# Project_bird_V2_1.net
KiCad netlist of a schematic drawn in EAGLE
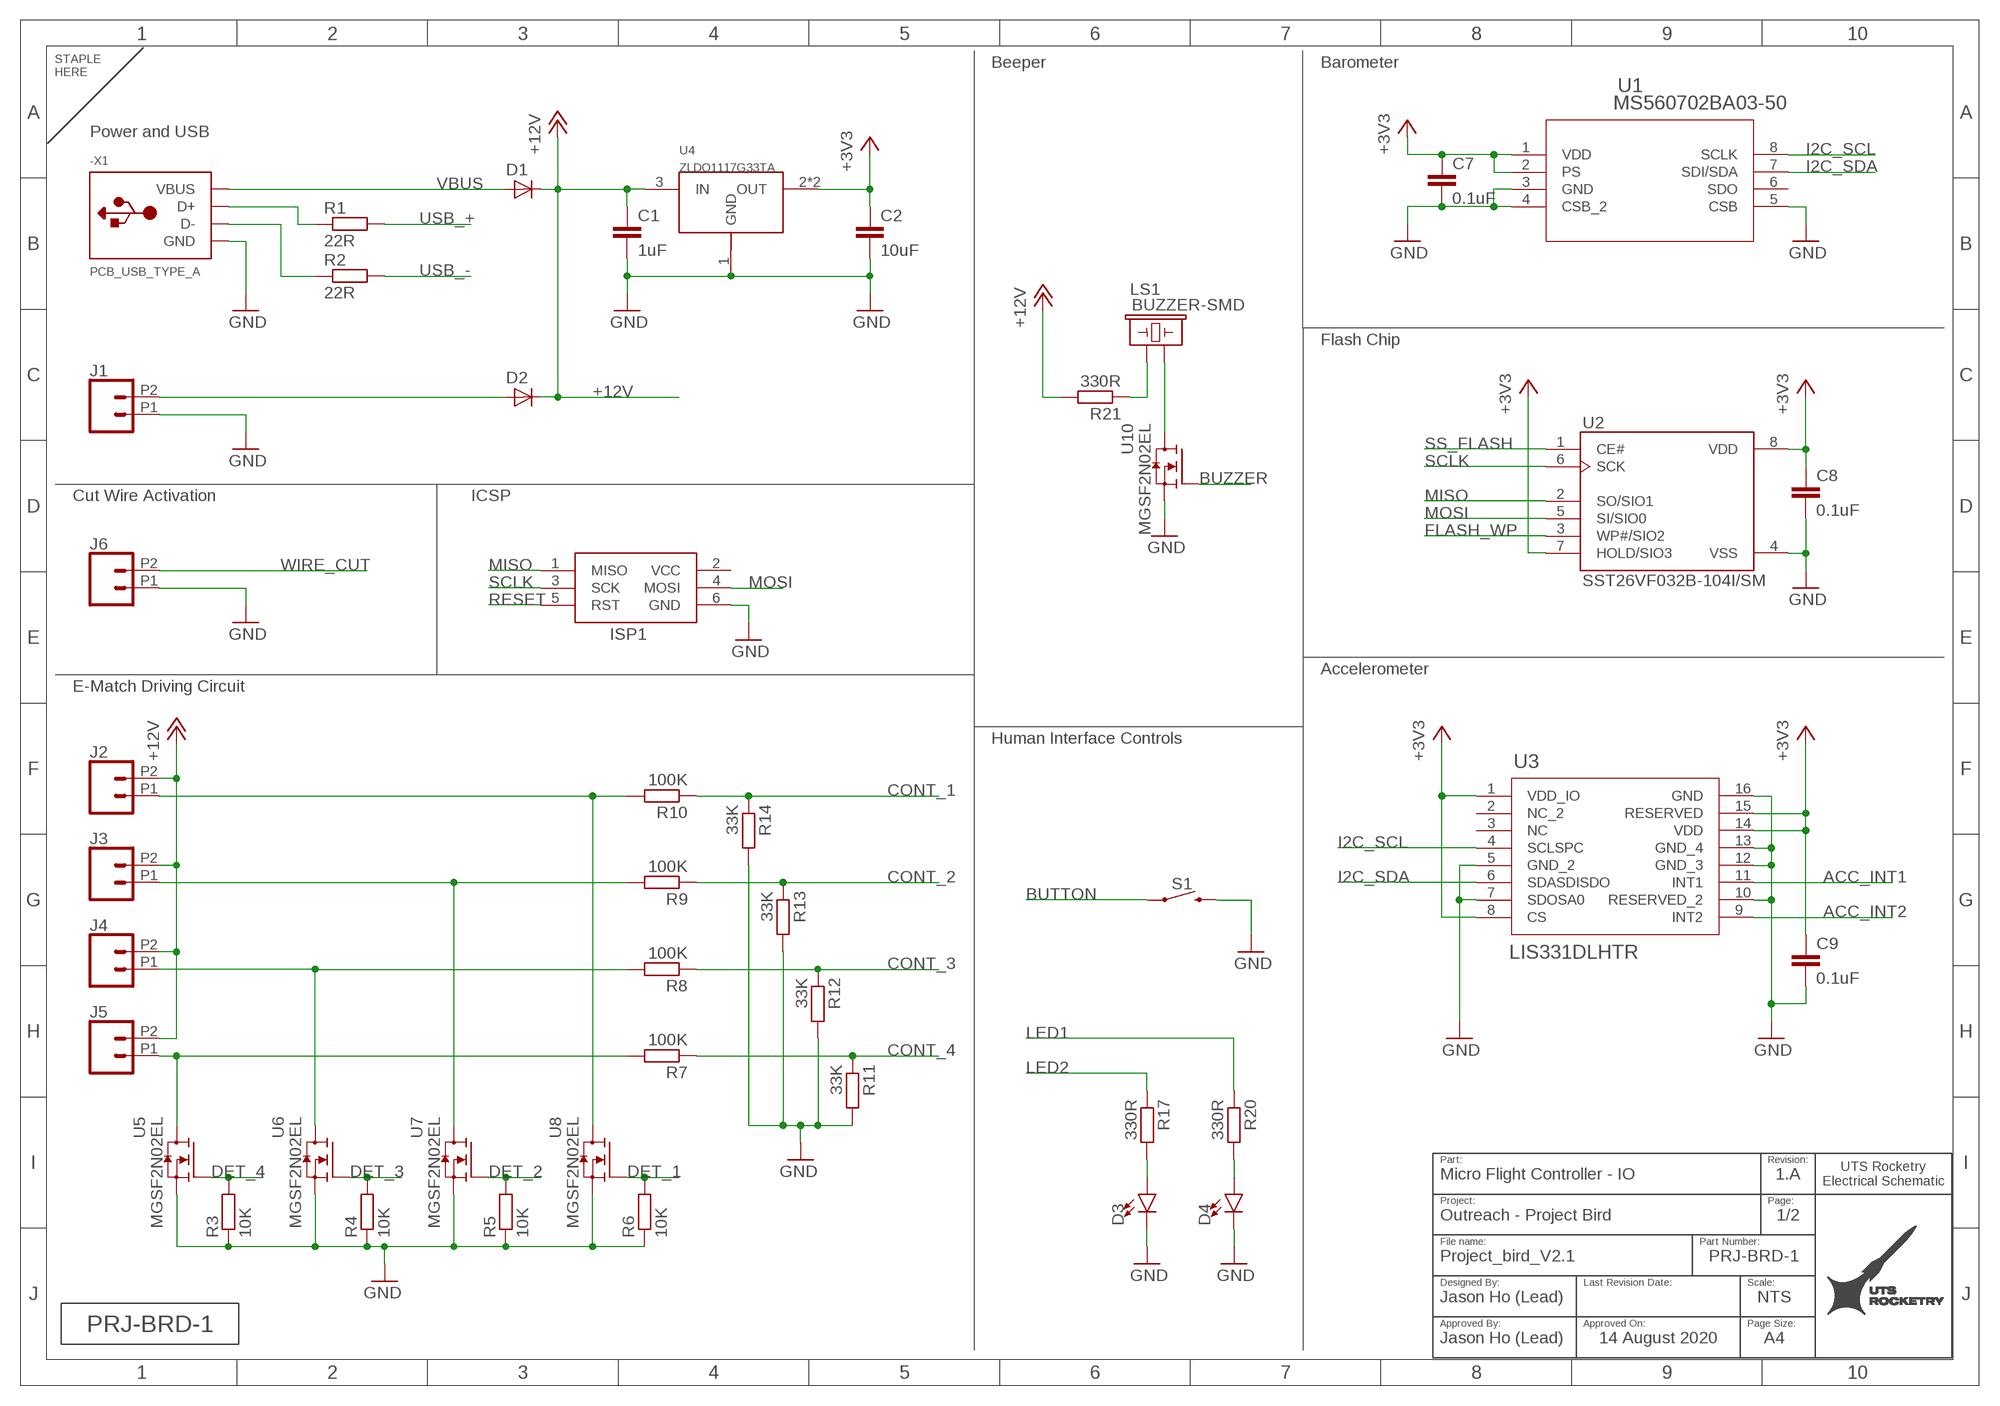
[diagram p0: schematic, sheet 1]
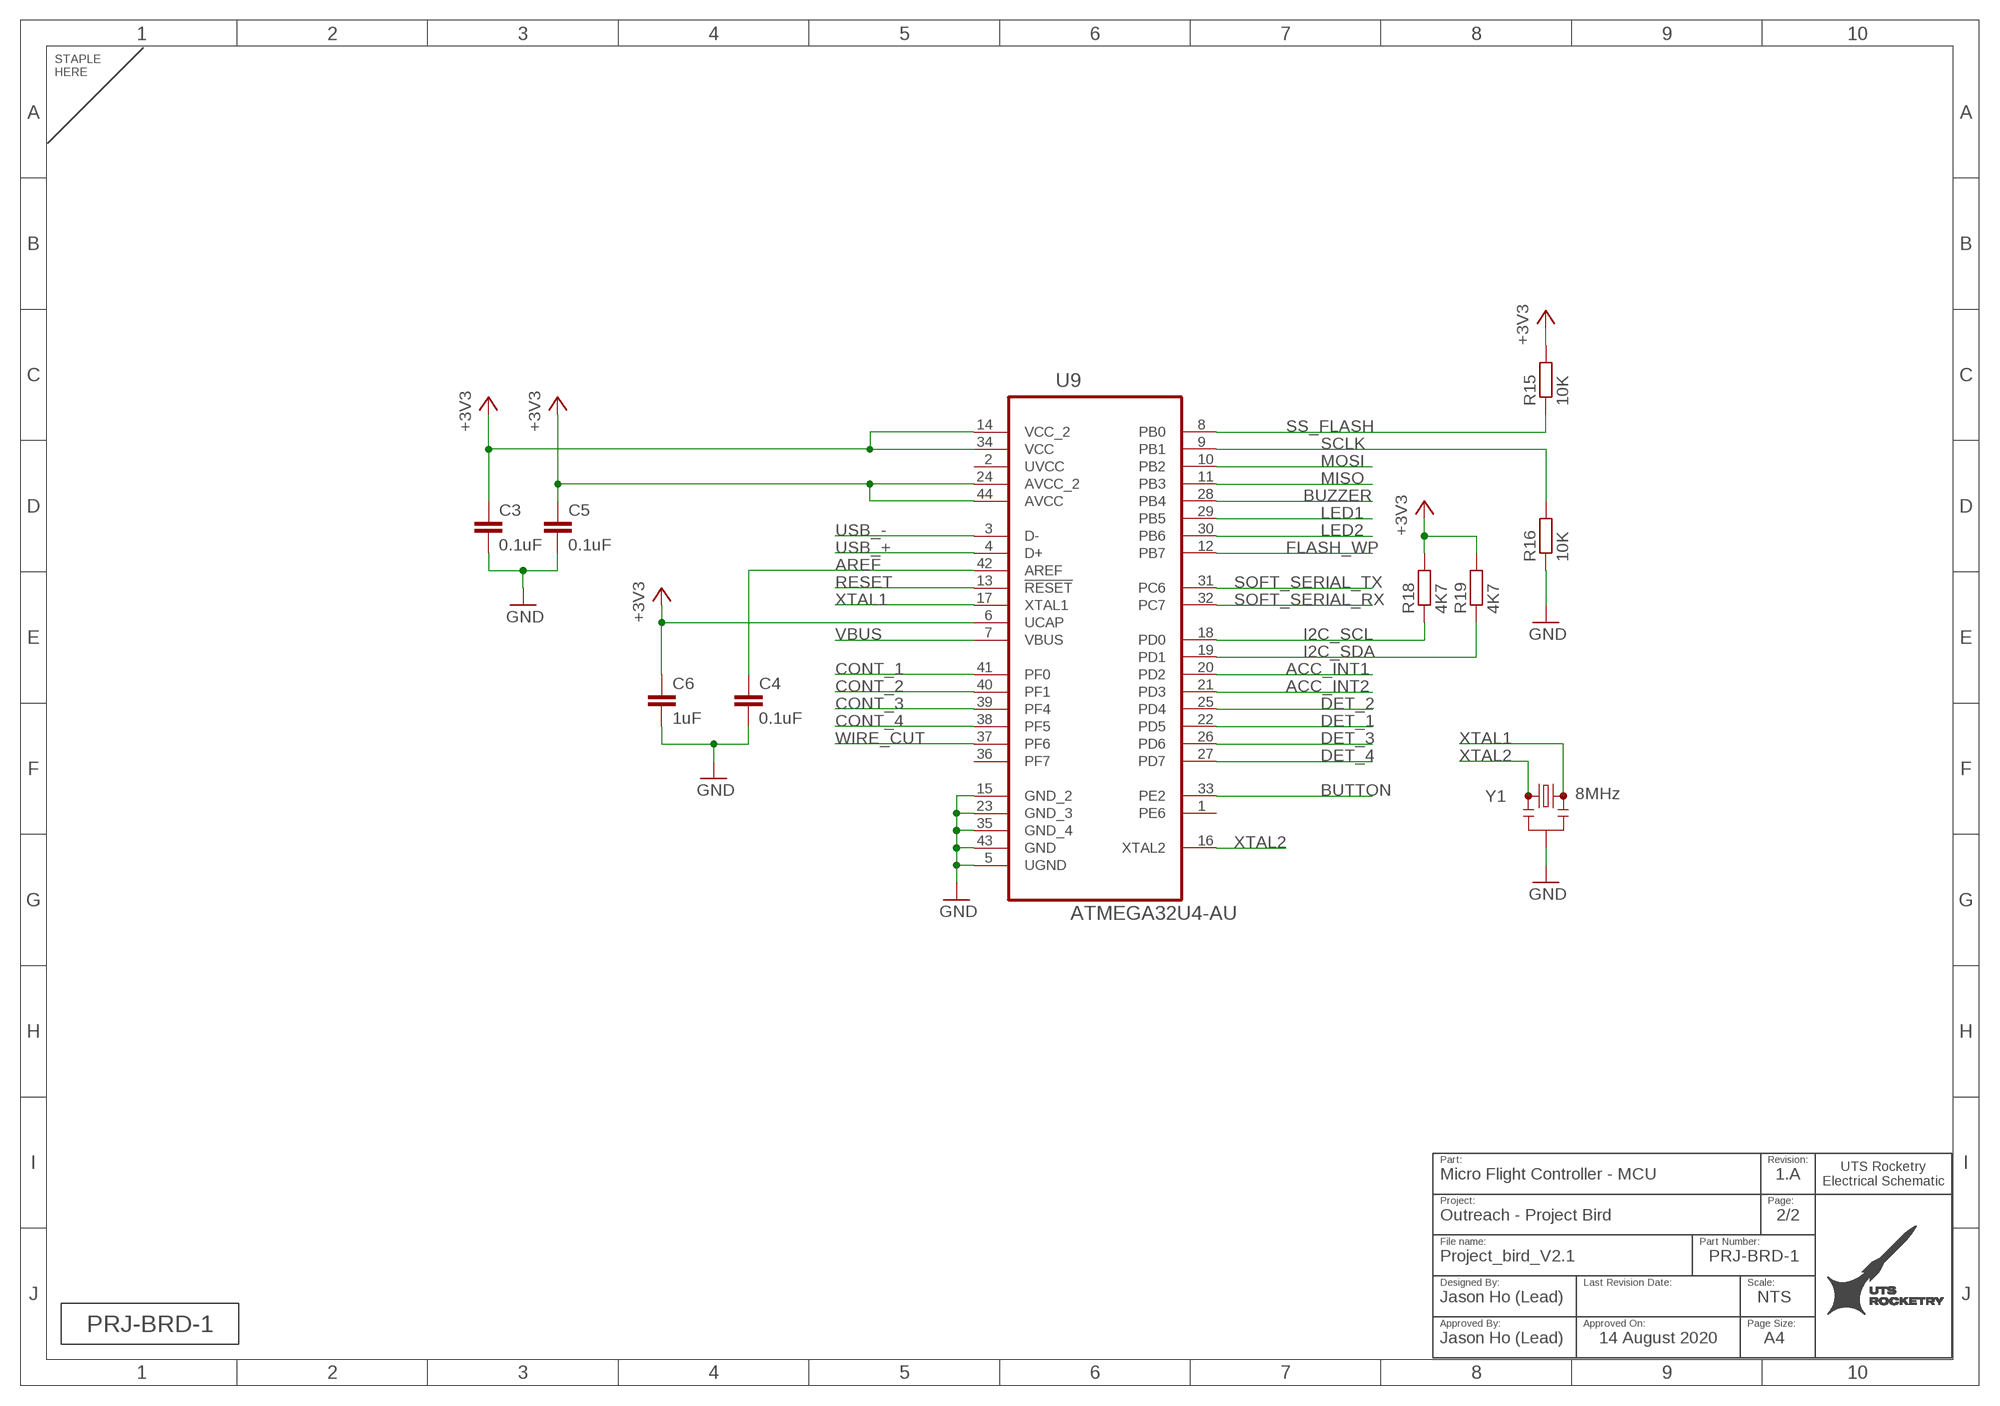
[diagram p1: schematic, sheet 2]

(export (version "E")
  (design (tool "Eeschema 10.0.6"))
  (components
    (comp (ref "C3")
      (value "0.1uF")
      (footprint "eagle-import:C0805K")
      (libsource (lib "eagle-import") (part "CAP_0805"))
    )
    (comp (ref "C4")
      (value "0.1uF")
      (footprint "eagle-import:C0805K")
      (libsource (lib "eagle-import") (part "CAP_0805"))
    )
    (comp (ref "C5")
      (value "0.1uF")
      (footprint "eagle-import:C0805K")
      (libsource (lib "eagle-import") (part "CAP_0805"))
    )
    (comp (ref "C6")
      (value "1uF")
      (footprint "eagle-import:C0805K")
      (libsource (lib "eagle-import") (part "CAP_0805"))
    )
    (comp (ref "R15")
      (value "10K")
      (footprint "eagle-import:R0805")
      (libsource (lib "eagle-import") (part "RES_0805"))
    )
    (comp (ref "R16")
      (value "10K")
      (footprint "eagle-import:R0805")
      (libsource (lib "eagle-import") (part "RES_0805"))
    )
    (comp (ref "R18")
      (value "4K7")
      (footprint "eagle-import:R0805")
      (libsource (lib "eagle-import") (part "RES_0805"))
    )
    (comp (ref "R19")
      (value "4K7")
      (footprint "eagle-import:R0805")
      (libsource (lib "eagle-import") (part "RES_0805"))
    )
    (comp (ref "U9")
      (value "ATMEGA32U4-AU")
      (footprint "eagle-import:QFP80P1200X1200X120-44N")
      (fields (field (name "MF") "Microchip Technology / Atmel"))
      (libsource (lib "eagle-import") (part "ATMEGA32U4-AU"))
    )
    (comp (ref "Y1")
      (value "8MHz")
      (footprint "eagle-import:RESONATOR-SMD-3.2X1.3")
      (libsource (lib "eagle-import") (part "RESONATOR-CSTCE8M00G55-R0"))
    )
    (comp (ref "-X1")
      (value "PCB_USB_TYPE_A")
      (footprint "eagle-import:USB_TYPE-A")
      (libsource (lib "eagle-import") (part "PCB_USB_TYPE_A"))
    )
    (comp (ref "C1")
      (value "1uF")
      (footprint "eagle-import:C0805K")
      (libsource (lib "eagle-import") (part "CAP_0805"))
    )
    (comp (ref "C2")
      (value "10uF")
      (footprint "eagle-import:C0805K")
      (libsource (lib "eagle-import") (part "CAP_0805"))
    )
    (comp (ref "C7")
      (value "0.1uF")
      (footprint "eagle-import:C0805K")
      (libsource (lib "eagle-import") (part "CAP_0805"))
    )
    (comp (ref "C8")
      (value "0.1uF")
      (footprint "eagle-import:C0805K")
      (libsource (lib "eagle-import") (part "CAP_0805"))
    )
    (comp (ref "C9")
      (value "0.1uF")
      (footprint "eagle-import:C0805K")
      (libsource (lib "eagle-import") (part "CAP_0805"))
    )
    (comp (ref "D1")
      (value "1A")
      (footprint "eagle-import:SOD-323F")
      (libsource (lib "eagle-import") (part "DIODESOD-323F"))
    )
    (comp (ref "D2")
      (value "1A")
      (footprint "eagle-import:SOD-323F")
      (libsource (lib "eagle-import") (part "DIODESOD-323F"))
    )
    (comp (ref "D3")
      (value "LED3MM-RED")
      (footprint "eagle-import:LED_3MM")
      (libsource (lib "eagle-import") (part "LED3MM-RED"))
    )
    (comp (ref "D4")
      (value "LED3MM-YELLOW")
      (footprint "eagle-import:LED_3MM")
      (libsource (lib "eagle-import") (part "LED3MM-YELLOW"))
    )
    (comp (ref "ISP1")
      (value "AVRISP-6")
      (footprint "eagle-import:AVRISP")
      (libsource (lib "eagle-import") (part "AVRISP-6"))
    )
    (comp (ref "J1")
      (value "CONN_022.54MM_SCREWTERM")
      (footprint "eagle-import:1X02_2.54_SCREWTERM")
      (libsource (lib "eagle-import") (part "CONN_022.54MM_SCREWTERM"))
    )
    (comp (ref "J2")
      (value "CONN_022.54MM_SCREWTERM")
      (footprint "eagle-import:1X02_2.54_SCREWTERM")
      (libsource (lib "eagle-import") (part "CONN_022.54MM_SCREWTERM"))
    )
    (comp (ref "J3")
      (value "CONN_022.54MM_SCREWTERM")
      (footprint "eagle-import:1X02_2.54_SCREWTERM")
      (libsource (lib "eagle-import") (part "CONN_022.54MM_SCREWTERM"))
    )
    (comp (ref "J4")
      (value "CONN_022.54MM_SCREWTERM")
      (footprint "eagle-import:1X02_2.54_SCREWTERM")
      (libsource (lib "eagle-import") (part "CONN_022.54MM_SCREWTERM"))
    )
    (comp (ref "J5")
      (value "CONN_022.54MM_SCREWTERM")
      (footprint "eagle-import:1X02_2.54_SCREWTERM")
      (libsource (lib "eagle-import") (part "CONN_022.54MM_SCREWTERM"))
    )
    (comp (ref "J6")
      (value "CONN_022.54MM_SCREWTERM")
      (footprint "eagle-import:1X02_2.54_SCREWTERM")
      (libsource (lib "eagle-import") (part "CONN_022.54MM_SCREWTERM"))
    )
    (comp (ref "LS1")
      (value "BUZZER-SMD")
      (footprint "eagle-import:BUZZER-CCV")
      (libsource (lib "eagle-import") (part "BUZZER-SMD"))
    )
    (comp (ref "R1")
      (value "22R")
      (footprint "eagle-import:R0805")
      (libsource (lib "eagle-import") (part "RES_0805"))
    )
    (comp (ref "R2")
      (value "22R")
      (footprint "eagle-import:R0805")
      (libsource (lib "eagle-import") (part "RES_0805"))
    )
    (comp (ref "R3")
      (value "10K")
      (footprint "eagle-import:R0805")
      (libsource (lib "eagle-import") (part "RES_0805"))
    )
    (comp (ref "R4")
      (value "10K")
      (footprint "eagle-import:R0805")
      (libsource (lib "eagle-import") (part "RES_0805"))
    )
    (comp (ref "R5")
      (value "10K")
      (footprint "eagle-import:R0805")
      (libsource (lib "eagle-import") (part "RES_0805"))
    )
    (comp (ref "R6")
      (value "10K")
      (footprint "eagle-import:R0805")
      (libsource (lib "eagle-import") (part "RES_0805"))
    )
    (comp (ref "R7")
      (value "100K")
      (footprint "eagle-import:R0805")
      (libsource (lib "eagle-import") (part "RES_0805"))
    )
    (comp (ref "R8")
      (value "100K")
      (footprint "eagle-import:R0805")
      (libsource (lib "eagle-import") (part "RES_0805"))
    )
    (comp (ref "R9")
      (value "100K")
      (footprint "eagle-import:R0805")
      (libsource (lib "eagle-import") (part "RES_0805"))
    )
    (comp (ref "R10")
      (value "100K")
      (footprint "eagle-import:R0805")
      (libsource (lib "eagle-import") (part "RES_0805"))
    )
    (comp (ref "R11")
      (value "33K")
      (footprint "eagle-import:R0805")
      (libsource (lib "eagle-import") (part "RES_0805"))
    )
    (comp (ref "R12")
      (value "33K")
      (footprint "eagle-import:R0805")
      (libsource (lib "eagle-import") (part "RES_0805"))
    )
    (comp (ref "R13")
      (value "33K")
      (footprint "eagle-import:R0805")
      (libsource (lib "eagle-import") (part "RES_0805"))
    )
    (comp (ref "R14")
      (value "33K")
      (footprint "eagle-import:R0805")
      (libsource (lib "eagle-import") (part "RES_0805"))
    )
    (comp (ref "R17")
      (value "330R")
      (footprint "eagle-import:R0805")
      (libsource (lib "eagle-import") (part "RES_0805"))
    )
    (comp (ref "R20")
      (value "330R")
      (footprint "eagle-import:R0805")
      (libsource (lib "eagle-import") (part "RES_0805"))
    )
    (comp (ref "R21")
      (value "330R")
      (footprint "eagle-import:R0805")
      (libsource (lib "eagle-import") (part "RES_0805"))
    )
    (comp (ref "S1")
      (value "MOMENTARY-SWITCH-SPST")
      (footprint "eagle-import:TACTILE_SWITCH_PTH_6.0MM")
      (libsource (lib "eagle-import") (part "MOMENTARY-SWITCH-SPST"))
    )
    (comp (ref "U1")
      (value "MS560702BA03-50")
      (footprint "eagle-import:SON8_MS5611")
      (fields (field (name "COPYRIGHT") "Copyright (C) 2016 Accelerated Designs. All rights reserved"))
      (libsource (lib "eagle-import") (part "MS560702BA03-50"))
    )
    (comp (ref "U2")
      (value "SST26VF032B-104I/SM")
      (footprint "eagle-import:SOIC127P794X203-8N")
      (fields (field (name "MF") "Microchip"))
      (libsource (lib "eagle-import") (part "SST26VF032B-104I/SM"))
    )
    (comp (ref "U3")
      (value "LIS331DLHTR")
      (footprint "eagle-import:LGA-16_3X3X1MM")
      (libsource (lib "eagle-import") (part "LIS331DLHTR"))
    )
    (comp (ref "U4")
      (value "ZLDO1117G33TA")
      (footprint "eagle-import:SOT223")
      (libsource (lib "eagle-import") (part "ZLDO1117G33TA"))
    )
    (comp (ref "U5")
      (value "MGSF2N02EL")
      (footprint "eagle-import:SOT-23-3")
      (libsource (lib "eagle-import") (part "MGSF2N02EL"))
    )
    (comp (ref "U6")
      (value "MGSF2N02EL")
      (footprint "eagle-import:SOT-23-3")
      (libsource (lib "eagle-import") (part "MGSF2N02EL"))
    )
    (comp (ref "U7")
      (value "MGSF2N02EL")
      (footprint "eagle-import:SOT-23-3")
      (libsource (lib "eagle-import") (part "MGSF2N02EL"))
    )
    (comp (ref "U8")
      (value "MGSF2N02EL")
      (footprint "eagle-import:SOT-23-3")
      (libsource (lib "eagle-import") (part "MGSF2N02EL"))
    )
    (comp (ref "U10")
      (value "MGSF2N02EL")
      (footprint "eagle-import:SOT-23-3")
      (libsource (lib "eagle-import") (part "MGSF2N02EL"))
    )
  )
  (nets
    (net (code "1") (name "+3V3") (class "Default")
      (node (ref "C2") (pin "1") (pinfunction "1_1") (pintype "passive"))
      (node (ref "C3") (pin "1") (pinfunction "1_1") (pintype "passive"))
      (node (ref "C5") (pin "1") (pinfunction "1_1") (pintype "passive"))
      (node (ref "C6") (pin "1") (pinfunction "1_1") (pintype "passive"))
      (node (ref "C7") (pin "1") (pinfunction "1_1") (pintype "passive"))
      (node (ref "C8") (pin "1") (pinfunction "1_1") (pintype "passive"))
      (node (ref "C9") (pin "1") (pinfunction "1_1") (pintype "passive"))
      (node (ref "R15") (pin "2") (pinfunction "2_2") (pintype "passive"))
      (node (ref "R18") (pin "2") (pinfunction "2_2") (pintype "passive"))
      (node (ref "R19") (pin "2") (pinfunction "2_2") (pintype "passive"))
      (node (ref "U1") (pin "1") (pinfunction "VDD_1") (pintype "power_in"))
      (node (ref "U1") (pin "2") (pinfunction "PS_2") (pintype "input"))
      (node (ref "U2") (pin "7") (pinfunction "HOLD/SIO3_7") (pintype "bidirectional"))
      (node (ref "U2") (pin "8") (pinfunction "VDD_8") (pintype "power_in"))
      (node (ref "U3") (pin "1") (pinfunction "VDD_IO_1") (pintype "power_in"))
      (node (ref "U3") (pin "14") (pinfunction "VDD_14") (pintype "power_in"))
      (node (ref "U3") (pin "15") (pinfunction "RESERVED_15") (pintype "passive"))
      (node (ref "U3") (pin "8") (pinfunction "CS_8") (pintype "passive"))
      (node (ref "U4") (pin "2") (pinfunction "OUT_2") (pintype "power_in"))
      (node (ref "U4") (pin "4") (pinfunction "OUT_4") (pintype "power_in"))
      (node (ref "U9") (pin "14") (pinfunction "VCC_2_14") (pintype "power_in"))
      (node (ref "U9") (pin "24") (pinfunction "AVCC_2_24") (pintype "power_in"))
      (node (ref "U9") (pin "34") (pinfunction "VCC_34") (pintype "power_in"))
      (node (ref "U9") (pin "44") (pinfunction "AVCC_44") (pintype "power_in"))
      (node (ref "U9") (pin "6") (pinfunction "UCAP_6") (pintype "power_in"))
    )
    (net (code "2") (name "+12V") (class "Default")
      (node (ref "C1") (pin "1") (pinfunction "1_1") (pintype "passive"))
      (node (ref "D1") (pin "C") (pinfunction "C_C") (pintype "passive"))
      (node (ref "D2") (pin "C") (pinfunction "C_C") (pintype "passive"))
      (node (ref "J2") (pin "P2") (pinfunction "2_P2") (pintype "passive"))
      (node (ref "J3") (pin "P2") (pinfunction "2_P2") (pintype "passive"))
      (node (ref "J4") (pin "P2") (pinfunction "2_P2") (pintype "passive"))
      (node (ref "J5") (pin "P2") (pinfunction "2_P2") (pintype "passive"))
      (node (ref "R21") (pin "2") (pinfunction "2_2") (pintype "passive"))
      (node (ref "U4") (pin "3") (pinfunction "IN_3") (pintype "power_in"))
    )
    (net (code "3") (name "ACC_INT1") (class "Default")
      (node (ref "U3") (pin "11") (pinfunction "INT1_11") (pintype "passive"))
      (node (ref "U9") (pin "20") (pinfunction "PD2_20") (pintype "bidirectional"))
    )
    (net (code "4") (name "ACC_INT2") (class "Default")
      (node (ref "U3") (pin "9") (pinfunction "INT2_9") (pintype "passive"))
      (node (ref "U9") (pin "21") (pinfunction "PD3_21") (pintype "bidirectional"))
    )
    (net (code "5") (name "AREF") (class "Default")
      (node (ref "C4") (pin "1") (pinfunction "1_1") (pintype "passive"))
      (node (ref "U9") (pin "42") (pinfunction "AREF_42") (pintype "input"))
    )
    (net (code "6") (name "BUTTON") (class "Default")
      (node (ref "S1") (pin "1") (pinfunction "1_1") (pintype "passive"))
      (node (ref "S1") (pin "2") (pinfunction "1_2") (pintype "passive"))
      (node (ref "U9") (pin "33") (pinfunction "PE2_33") (pintype "bidirectional"))
    )
    (net (code "7") (name "BUZZER") (class "Default")
      (node (ref "U10") (pin "1") (pinfunction "G_1") (pintype "passive"))
      (node (ref "U9") (pin "28") (pinfunction "PB4_28") (pintype "bidirectional"))
    )
    (net (code "8") (name "CONT_1") (class "Default")
      (node (ref "R10") (pin "1") (pinfunction "1_1") (pintype "passive"))
      (node (ref "R14") (pin "1") (pinfunction "1_1") (pintype "passive"))
      (node (ref "U9") (pin "41") (pinfunction "PF0_41") (pintype "bidirectional"))
    )
    (net (code "9") (name "CONT_2") (class "Default")
      (node (ref "R13") (pin "1") (pinfunction "1_1") (pintype "passive"))
      (node (ref "R9") (pin "1") (pinfunction "1_1") (pintype "passive"))
      (node (ref "U9") (pin "40") (pinfunction "PF1_40") (pintype "bidirectional"))
    )
    (net (code "10") (name "CONT_3") (class "Default")
      (node (ref "R12") (pin "1") (pinfunction "1_1") (pintype "passive"))
      (node (ref "R8") (pin "1") (pinfunction "1_1") (pintype "passive"))
      (node (ref "U9") (pin "39") (pinfunction "PF4_39") (pintype "bidirectional"))
    )
    (net (code "11") (name "CONT_4") (class "Default")
      (node (ref "R11") (pin "1") (pinfunction "1_1") (pintype "passive"))
      (node (ref "R7") (pin "1") (pinfunction "1_1") (pintype "passive"))
      (node (ref "U9") (pin "38") (pinfunction "PF5_38") (pintype "bidirectional"))
    )
    (net (code "12") (name "DET_1") (class "Default")
      (node (ref "R6") (pin "2") (pinfunction "2_2") (pintype "passive"))
      (node (ref "U8") (pin "1") (pinfunction "G_1") (pintype "passive"))
      (node (ref "U9") (pin "22") (pinfunction "PD5_22") (pintype "bidirectional"))
    )
    (net (code "13") (name "DET_2") (class "Default")
      (node (ref "R5") (pin "2") (pinfunction "2_2") (pintype "passive"))
      (node (ref "U7") (pin "1") (pinfunction "G_1") (pintype "passive"))
      (node (ref "U9") (pin "25") (pinfunction "PD4_25") (pintype "bidirectional"))
    )
    (net (code "14") (name "DET_3") (class "Default")
      (node (ref "R4") (pin "2") (pinfunction "2_2") (pintype "passive"))
      (node (ref "U6") (pin "1") (pinfunction "G_1") (pintype "passive"))
      (node (ref "U9") (pin "26") (pinfunction "PD6_26") (pintype "bidirectional"))
    )
    (net (code "15") (name "DET_4") (class "Default")
      (node (ref "R3") (pin "2") (pinfunction "2_2") (pintype "passive"))
      (node (ref "U5") (pin "1") (pinfunction "G_1") (pintype "passive"))
      (node (ref "U9") (pin "27") (pinfunction "PD7_27") (pintype "bidirectional"))
    )
    (net (code "16") (name "FLASH_WP") (class "Default")
      (node (ref "U2") (pin "3") (pinfunction "WP#/SIO2_3") (pintype "bidirectional"))
      (node (ref "U9") (pin "12") (pinfunction "PB7_12") (pintype "bidirectional"))
    )
    (net (code "17") (name "GND") (class "Default")
      (node (ref "-X1") (pin "GND") (pinfunction "GND_GND") (pintype "power_in"))
      (node (ref "C1") (pin "2") (pinfunction "2_2") (pintype "passive"))
      (node (ref "C2") (pin "2") (pinfunction "2_2") (pintype "passive"))
      (node (ref "C3") (pin "2") (pinfunction "2_2") (pintype "passive"))
      (node (ref "C4") (pin "2") (pinfunction "2_2") (pintype "passive"))
      (node (ref "C5") (pin "2") (pinfunction "2_2") (pintype "passive"))
      (node (ref "C6") (pin "2") (pinfunction "2_2") (pintype "passive"))
      (node (ref "C7") (pin "2") (pinfunction "2_2") (pintype "passive"))
      (node (ref "C8") (pin "2") (pinfunction "2_2") (pintype "passive"))
      (node (ref "C9") (pin "2") (pinfunction "2_2") (pintype "passive"))
      (node (ref "D3") (pin "K") (pinfunction "C_K") (pintype "passive"))
      (node (ref "D4") (pin "K") (pinfunction "C_K") (pintype "passive"))
      (node (ref "ISP1") (pin "6") (pinfunction "GND_6") (pintype "power_in"))
      (node (ref "J1") (pin "P1") (pinfunction "1_P1") (pintype "passive"))
      (node (ref "J6") (pin "P1") (pinfunction "1_P1") (pintype "passive"))
      (node (ref "R11") (pin "2") (pinfunction "2_2") (pintype "passive"))
      (node (ref "R12") (pin "2") (pinfunction "2_2") (pintype "passive"))
      (node (ref "R13") (pin "2") (pinfunction "2_2") (pintype "passive"))
      (node (ref "R14") (pin "2") (pinfunction "2_2") (pintype "passive"))
      (node (ref "R16") (pin "1") (pinfunction "1_1") (pintype "passive"))
      (node (ref "R3") (pin "1") (pinfunction "1_1") (pintype "passive"))
      (node (ref "R4") (pin "1") (pinfunction "1_1") (pintype "passive"))
      (node (ref "R5") (pin "1") (pinfunction "1_1") (pintype "passive"))
      (node (ref "R6") (pin "1") (pinfunction "1_1") (pintype "passive"))
      (node (ref "S1") (pin "3") (pinfunction "2_3") (pintype "passive"))
      (node (ref "S1") (pin "4") (pinfunction "2_4") (pintype "passive"))
      (node (ref "U1") (pin "3") (pinfunction "GND_3") (pintype "passive"))
      (node (ref "U1") (pin "4") (pinfunction "CSB_2_4") (pintype "input"))
      (node (ref "U1") (pin "5") (pinfunction "CSB_5") (pintype "input"))
      (node (ref "U10") (pin "2") (pinfunction "S_2") (pintype "passive"))
      (node (ref "U2") (pin "4") (pinfunction "VSS_4") (pintype "power_in"))
      (node (ref "U3") (pin "10") (pinfunction "RESERVED_2_10") (pintype "passive"))
      (node (ref "U3") (pin "12") (pinfunction "GND_3_12") (pintype "power_in"))
      (node (ref "U3") (pin "13") (pinfunction "GND_4_13") (pintype "power_in"))
      (node (ref "U3") (pin "16") (pinfunction "GND_16") (pintype "power_in"))
      (node (ref "U3") (pin "5") (pinfunction "GND_2_5") (pintype "power_in"))
      (node (ref "U3") (pin "7") (pinfunction "SDOSA0_7") (pintype "output"))
      (node (ref "U4") (pin "1") (pinfunction "GND_1") (pintype "power_in"))
      (node (ref "U5") (pin "2") (pinfunction "S_2") (pintype "passive"))
      (node (ref "U6") (pin "2") (pinfunction "S_2") (pintype "passive"))
      (node (ref "U7") (pin "2") (pinfunction "S_2") (pintype "passive"))
      (node (ref "U8") (pin "2") (pinfunction "S_2") (pintype "passive"))
      (node (ref "U9") (pin "15") (pinfunction "GND_2_15") (pintype "passive"))
      (node (ref "U9") (pin "23") (pinfunction "GND_3_23") (pintype "passive"))
      (node (ref "U9") (pin "35") (pinfunction "GND_4_35") (pintype "passive"))
      (node (ref "U9") (pin "43") (pinfunction "GND_43") (pintype "passive"))
      (node (ref "U9") (pin "5") (pinfunction "UGND_5") (pintype "passive"))
      (node (ref "Y1") (pin "2") (pinfunction "2_2") (pintype "passive"))
    )
    (net (code "18") (name "I2C_SCL") (class "Default")
      (node (ref "R18") (pin "1") (pinfunction "1_1") (pintype "passive"))
      (node (ref "U1") (pin "8") (pinfunction "SCLK_8") (pintype "bidirectional"))
      (node (ref "U3") (pin "4") (pinfunction "SCLSPC_4") (pintype "passive"))
      (node (ref "U9") (pin "18") (pinfunction "PD0_18") (pintype "bidirectional"))
    )
    (net (code "19") (name "I2C_SDA") (class "Default")
      (node (ref "R19") (pin "1") (pinfunction "1_1") (pintype "passive"))
      (node (ref "U1") (pin "7") (pinfunction "SDI/SDA_7") (pintype "bidirectional"))
      (node (ref "U3") (pin "6") (pinfunction "SDASDISDO_6") (pintype "bidirectional"))
      (node (ref "U9") (pin "19") (pinfunction "PD1_19") (pintype "bidirectional"))
    )
    (net (code "20") (name "LED1") (class "Default")
      (node (ref "R20") (pin "1") (pinfunction "1_1") (pintype "passive"))
      (node (ref "U9") (pin "29") (pinfunction "PB5_29") (pintype "bidirectional"))
    )
    (net (code "21") (name "LED2") (class "Default")
      (node (ref "R17") (pin "1") (pinfunction "1_1") (pintype "passive"))
      (node (ref "U9") (pin "30") (pinfunction "PB6_30") (pintype "bidirectional"))
    )
    (net (code "22") (name "MISO") (class "Default")
      (node (ref "ISP1") (pin "1") (pinfunction "MISO_1") (pintype "input"))
      (node (ref "U2") (pin "2") (pinfunction "SO/SIO1_2") (pintype "bidirectional"))
      (node (ref "U9") (pin "11") (pinfunction "PB3_11") (pintype "bidirectional"))
    )
    (net (code "23") (name "MOSI") (class "Default")
      (node (ref "ISP1") (pin "4") (pinfunction "MOSI_4") (pintype "output"))
      (node (ref "U2") (pin "5") (pinfunction "SI/SIO0_5") (pintype "bidirectional"))
      (node (ref "U9") (pin "10") (pinfunction "PB2_10") (pintype "bidirectional"))
    )
    (net (code "24") (name "Net-(-X1-PadD+)") (class "Default")
      (node (ref "-X1") (pin "D+") (pinfunction "D+_D+") (pintype "bidirectional"))
      (node (ref "R1") (pin "1") (pinfunction "1_1") (pintype "passive"))
    )
    (net (code "25") (name "Net-(-X1-PadD-)") (class "Default")
      (node (ref "-X1") (pin "D-") (pinfunction "D-_D-") (pintype "bidirectional"))
      (node (ref "R2") (pin "1") (pinfunction "1_1") (pintype "passive"))
    )
    (net (code "26") (name "Net-(D3-PadA)") (class "Default")
      (node (ref "D3") (pin "A") (pinfunction "A_A") (pintype "passive"))
      (node (ref "R17") (pin "2") (pinfunction "2_2") (pintype "passive"))
    )
    (net (code "27") (name "Net-(D4-PadA)") (class "Default")
      (node (ref "D4") (pin "A") (pinfunction "A_A") (pintype "passive"))
      (node (ref "R20") (pin "2") (pinfunction "2_2") (pintype "passive"))
    )
    (net (code "28") (name "Net-(J1-2)") (class "Default")
      (node (ref "D2") (pin "A") (pinfunction "A_A") (pintype "passive"))
      (node (ref "J1") (pin "P2") (pinfunction "2_P2") (pintype "passive"))
    )
    (net (code "29") (name "Net-(J2-1)") (class "Default")
      (node (ref "J2") (pin "P1") (pinfunction "1_P1") (pintype "passive"))
      (node (ref "R10") (pin "2") (pinfunction "2_2") (pintype "passive"))
      (node (ref "U8") (pin "3") (pinfunction "D_3") (pintype "passive"))
    )
    (net (code "30") (name "Net-(J3-1)") (class "Default")
      (node (ref "J3") (pin "P1") (pinfunction "1_P1") (pintype "passive"))
      (node (ref "R9") (pin "2") (pinfunction "2_2") (pintype "passive"))
      (node (ref "U7") (pin "3") (pinfunction "D_3") (pintype "passive"))
    )
    (net (code "31") (name "Net-(J4-1)") (class "Default")
      (node (ref "J4") (pin "P1") (pinfunction "1_P1") (pintype "passive"))
      (node (ref "R8") (pin "2") (pinfunction "2_2") (pintype "passive"))
      (node (ref "U6") (pin "3") (pinfunction "D_3") (pintype "passive"))
    )
    (net (code "32") (name "Net-(J5-1)") (class "Default")
      (node (ref "J5") (pin "P1") (pinfunction "1_P1") (pintype "passive"))
      (node (ref "R7") (pin "2") (pinfunction "2_2") (pintype "passive"))
      (node (ref "U5") (pin "3") (pinfunction "D_3") (pintype "passive"))
    )
    (net (code "33") (name "Net-(LS1-1)") (class "Default")
      (node (ref "LS1") (pin "+") (pinfunction "1_+") (pintype "passive"))
      (node (ref "R21") (pin "1") (pinfunction "1_1") (pintype "passive"))
    )
    (net (code "34") (name "Net-(LS1-2)") (class "Default")
      (node (ref "LS1") (pin "-") (pinfunction "2_-") (pintype "passive"))
      (node (ref "U10") (pin "3") (pinfunction "D_3") (pintype "passive"))
    )
    (net (code "35") (name "RESET") (class "Default")
      (node (ref "ISP1") (pin "5") (pinfunction "RST_5") (pintype "output"))
      (node (ref "U9") (pin "13") (pinfunction "~{RESET}_13") (pintype "input"))
    )
    (net (code "36") (name "SCLK") (class "Default")
      (node (ref "ISP1") (pin "3") (pinfunction "SCK_3") (pintype "output"))
      (node (ref "R16") (pin "2") (pinfunction "2_2") (pintype "passive"))
      (node (ref "U2") (pin "6") (pinfunction "SCK_6") (pintype "bidirectional"))
      (node (ref "U9") (pin "9") (pinfunction "PB1_9") (pintype "bidirectional"))
    )
    (net (code "37") (name "SOFT_SERIAL_RX") (class "Default")
      (node (ref "U9") (pin "32") (pinfunction "PC7_32") (pintype "bidirectional"))
    )
    (net (code "38") (name "SOFT_SERIAL_TX") (class "Default")
      (node (ref "U9") (pin "31") (pinfunction "PC6_31") (pintype "bidirectional"))
    )
    (net (code "39") (name "SS_FLASH") (class "Default")
      (node (ref "R15") (pin "1") (pinfunction "1_1") (pintype "passive"))
      (node (ref "U2") (pin "1") (pinfunction "CE#_1") (pintype "bidirectional"))
      (node (ref "U9") (pin "8") (pinfunction "PB0_8") (pintype "bidirectional"))
    )
    (net (code "40") (name "USB_+") (class "Default")
      (node (ref "R1") (pin "2") (pinfunction "2_2") (pintype "passive"))
      (node (ref "U9") (pin "4") (pinfunction "D+_4") (pintype "passive"))
    )
    (net (code "41") (name "USB_-") (class "Default")
      (node (ref "R2") (pin "2") (pinfunction "2_2") (pintype "passive"))
      (node (ref "U9") (pin "3") (pinfunction "D-_3") (pintype "passive"))
    )
    (net (code "42") (name "UVCC") (class "Default")
      (node (ref "U9") (pin "2") (pinfunction "UVCC_2") (pintype "power_in"))
    )
    (net (code "43") (name "VBUS") (class "Default")
      (node (ref "-X1") (pin "VBUS") (pinfunction "VBUS_VBUS") (pintype "power_in"))
      (node (ref "D1") (pin "A") (pinfunction "A_A") (pintype "passive"))
      (node (ref "U9") (pin "7") (pinfunction "VBUS_7") (pintype "input"))
    )
    (net (code "44") (name "VCC") (class "Default")
      (node (ref "ISP1") (pin "2") (pinfunction "VCC_2") (pintype "power_in"))
    )
    (net (code "45") (name "WIRE_CUT") (class "Default")
      (node (ref "J6") (pin "P2") (pinfunction "2_P2") (pintype "passive"))
      (node (ref "U9") (pin "37") (pinfunction "PF6_37") (pintype "bidirectional"))
    )
    (net (code "46") (name "XTAL1") (class "Default")
      (node (ref "U9") (pin "17") (pinfunction "XTAL1_17") (pintype "input"))
      (node (ref "Y1") (pin "3") (pinfunction "3_3") (pintype "passive"))
    )
    (net (code "47") (name "XTAL2") (class "Default")
      (node (ref "U9") (pin "16") (pinfunction "XTAL2_16") (pintype "output"))
      (node (ref "Y1") (pin "1") (pinfunction "1_1") (pintype "passive"))
    )
    (net (code "48") (name "unconnected-(U1-SDO-Pad6)") (class "Default")
      (node (ref "U1") (pin "6") (pinfunction "SDO_6") (pintype "output"))
    )
    (net (code "49") (name "unconnected-(U3-NC-Pad3)") (class "Default")
      (node (ref "U3") (pin "3") (pinfunction "NC_3") (pintype "no_connect"))
    )
    (net (code "50") (name "unconnected-(U3-NC_2-Pad2)") (class "Default")
      (node (ref "U3") (pin "2") (pinfunction "NC_2_2") (pintype "no_connect"))
    )
    (net (code "51") (name "unconnected-(U9-PE6-Pad1)") (class "Default")
      (node (ref "U9") (pin "1") (pinfunction "PE6_1") (pintype "bidirectional"))
    )
    (net (code "52") (name "unconnected-(U9-PF7-Pad36)") (class "Default")
      (node (ref "U9") (pin "36") (pinfunction "PF7_36") (pintype "bidirectional"))
    )
  )
)
